# Inverter.net
KiCad netlist of a schematic drawn in Altium Designer
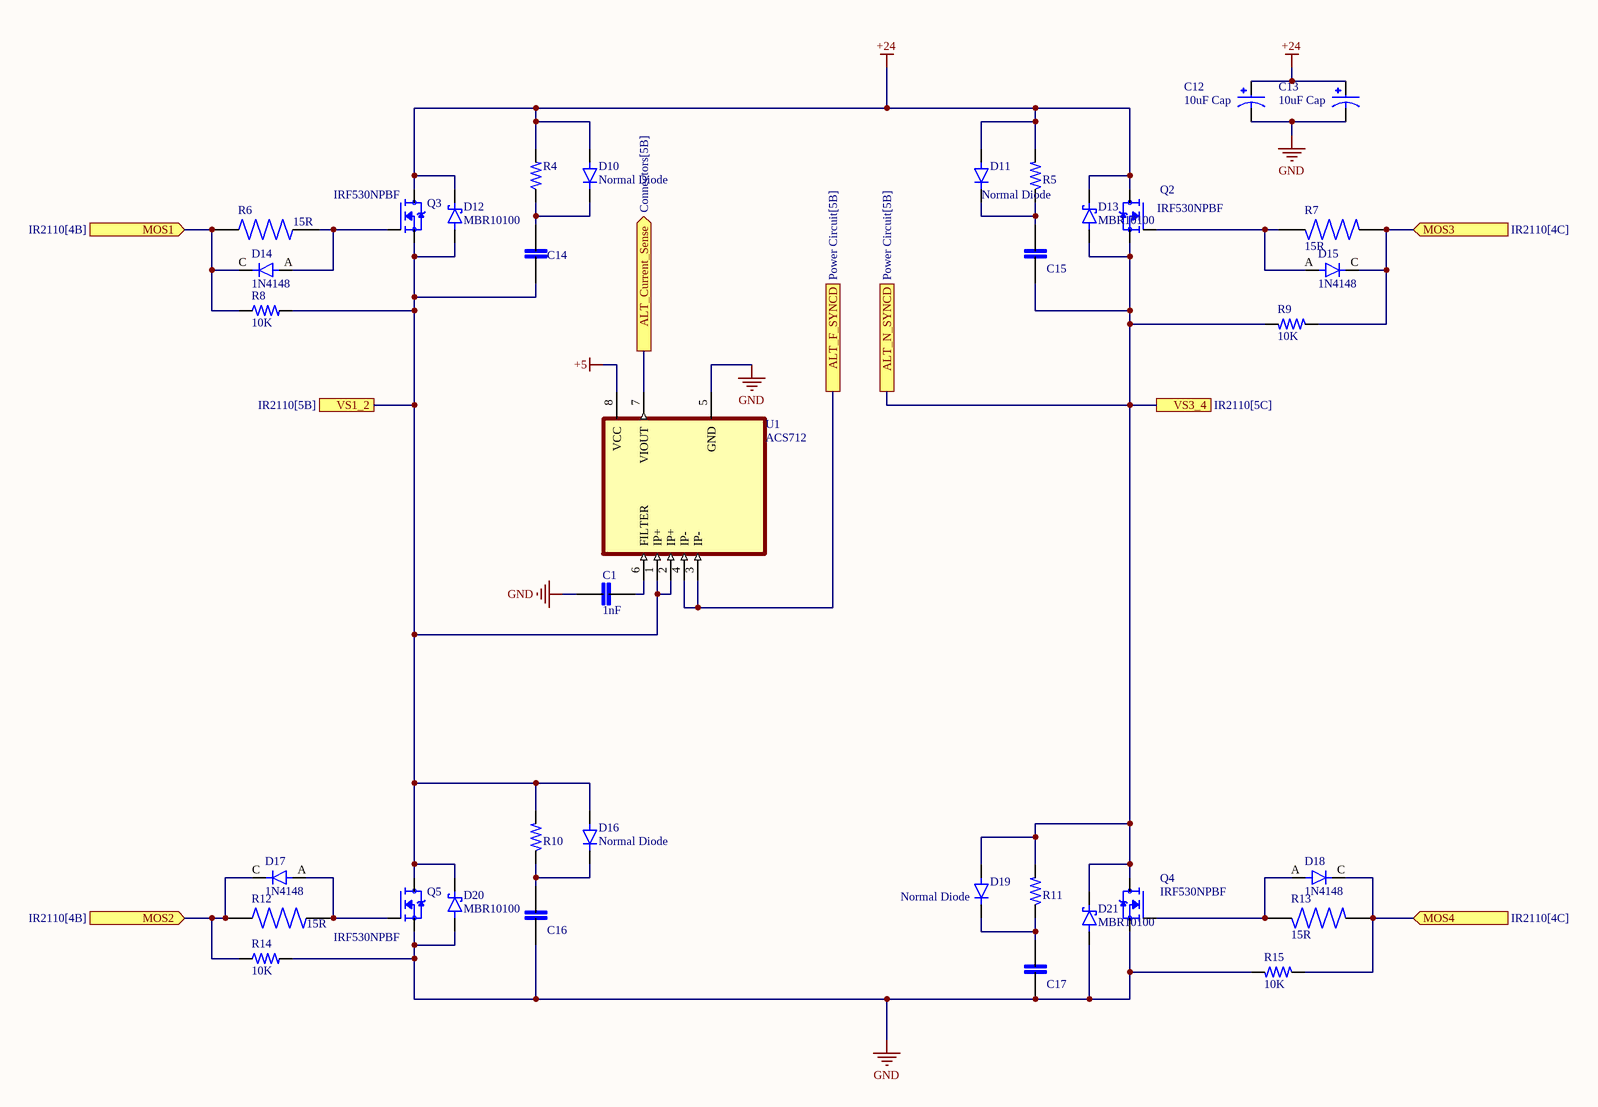
[diagram p0: Inverter.SchDoc]

(export (version "E")
  (design (tool "Eeschema 10.0.6"))
  (components
    (comp (ref "C1")
      (value "1nF")
      (footprint "Ceramic Capacitor")
      (fields (field (name "MP") "LD051A121KAB2A") (field (name "MF") "AVX"))
      (libsource (lib "Capacitors Through Hole") (part "Ceramic Capacitor"))
    )
    (comp (ref "C12")
      (value "10uF Cap")
      (footprint "2200uF_Cap")
      (description "CAP ALUM 10UF 20% 50V RADIAL")
      (fields (field (name "MP") "ECE-A1HN100UI") (field (name "MF") "Panasonic"))
      (libsource (lib "MySCH_Library") (part "10uF Cap"))
    )
    (comp (ref "C13")
      (value "10uF Cap")
      (footprint "2200uF_Cap")
      (description "CAP ALUM 10UF 20% 50V RADIAL")
      (fields (field (name "MP") "ECE-A1HN100UI") (field (name "MF") "Panasonic"))
      (libsource (lib "MySCH_Library") (part "10uF Cap"))
    )
    (comp (ref "C14")
      (value "Ceramic Capacitor")
      (footprint "Ceramic Capacitor")
      (fields (field (name "MP") "LD051A121KAB2A") (field (name "MF") "AVX"))
      (libsource (lib "") (part "Ceramic Capacitor_1"))
    )
    (comp (ref "C15")
      (value "Ceramic Capacitor")
      (footprint "Ceramic Capacitor")
      (fields (field (name "MP") "LD051A121KAB2A") (field (name "MF") "AVX"))
      (libsource (lib "Capacitors Through Hole") (part "Ceramic Capacitor"))
    )
    (comp (ref "C16")
      (value "Ceramic Capacitor")
      (footprint "Ceramic Capacitor")
      (fields (field (name "MP") "LD051A121KAB2A") (field (name "MF") "AVX"))
      (libsource (lib "Capacitors Through Hole") (part "Ceramic Capacitor"))
    )
    (comp (ref "C17")
      (value "Ceramic Capacitor")
      (footprint "Ceramic Capacitor")
      (fields (field (name "MP") "LD051A121KAB2A") (field (name "MF") "AVX"))
      (libsource (lib "Capacitors Through Hole") (part "Ceramic Capacitor"))
    )
    (comp (ref "D10")
      (value "Normal Diode")
      (footprint "Common Trhough Hole")
      (fields (field (name "MF") "NTE Electronics, Inc.") (field (name "MP") "1N4007"))
      (libsource (lib "Diodes Through Hole") (part "Normal Diode"))
    )
    (comp (ref "D11")
      (value "Normal Diode")
      (footprint "Common Trhough Hole")
      (fields (field (name "MF") "NTE Electronics, Inc.") (field (name "MP") "1N4007"))
      (libsource (lib "Diodes Through Hole") (part "Normal Diode"))
    )
    (comp (ref "D12")
      (value "MBR10100")
      (footprint "MBR10100")
      (fields (field (name "MF") "Diodes Inc.") (field (name "MP") "1N5817-T"))
      (libsource (lib "Diodes Through Hole") (part "MBR10100"))
    )
    (comp (ref "D13")
      (value "MBR10100")
      (footprint "MBR10100")
      (fields (field (name "MF") "Diodes Inc.") (field (name "MP") "1N5817-T"))
      (libsource (lib "Diodes Through Hole") (part "MBR10100"))
    )
    (comp (ref "D14")
      (value "1N4148")
      (footprint "1N4007 DIODE")
      (description "Diode Standard 1000 V 1A Through Hole DO-41")
      (fields (field (name "MF") "NTE Electronics, Inc.") (field (name "MP") "1N4007"))
      (libsource (lib "MySCH_Library") (part "1N4007"))
    )
    (comp (ref "D15")
      (value "1N4148")
      (footprint "1N4007 DIODE")
      (description "Diode Standard 1000 V 1A Through Hole DO-41")
      (fields (field (name "MF") "NTE Electronics, Inc.") (field (name "MP") "1N4007"))
      (libsource (lib "MySCH_Library") (part "1N4007"))
    )
    (comp (ref "D16")
      (value "Normal Diode")
      (footprint "Common Trhough Hole")
      (fields (field (name "MF") "NTE Electronics, Inc.") (field (name "MP") "1N4007"))
      (libsource (lib "Diodes Through Hole") (part "Normal Diode"))
    )
    (comp (ref "D17")
      (value "1N4148")
      (footprint "1N4007 DIODE")
      (description "Diode Standard 1000 V 1A Through Hole DO-41")
      (fields (field (name "MF") "NTE Electronics, Inc.") (field (name "MP") "1N4007"))
      (libsource (lib "MySCH_Library") (part "1N4007"))
    )
    (comp (ref "D18")
      (value "1N4148")
      (footprint "1N4007 DIODE")
      (description "Diode Standard 1000 V 1A Through Hole DO-41")
      (fields (field (name "MF") "NTE Electronics, Inc.") (field (name "MP") "1N4007"))
      (libsource (lib "MySCH_Library") (part "1N4007"))
    )
    (comp (ref "D19")
      (value "Normal Diode")
      (footprint "Common Trhough Hole")
      (fields (field (name "MF") "NTE Electronics, Inc.") (field (name "MP") "1N4007"))
      (libsource (lib "Diodes Through Hole") (part "Normal Diode"))
    )
    (comp (ref "D20")
      (value "MBR10100")
      (footprint "MBR10100")
      (fields (field (name "MF") "Diodes Inc.") (field (name "MP") "1N5817-T"))
      (libsource (lib "Diodes Through Hole") (part "MBR10100"))
    )
    (comp (ref "D21")
      (value "MBR10100")
      (footprint "MBR10100")
      (fields (field (name "MF") "Diodes Inc.") (field (name "MP") "1N5817-T"))
      (libsource (lib "Diodes Through Hole") (part "MBR10100"))
    )
    (comp (ref "Q2")
      (value "IRF530NPBF")
      (footprint "IRF530N")
      (fields (field (name "MF") "Infineon Technologies"))
      (libsource (lib "MySCH_Library") (part "IRF530NPBF"))
    )
    (comp (ref "Q3")
      (value "IRF530NPBF")
      (footprint "IRF530N")
      (fields (field (name "MF") "Infineon Technologies"))
      (libsource (lib "MySCH_Library") (part "IRF530NPBF"))
    )
    (comp (ref "Q4")
      (value "IRF530NPBF")
      (footprint "IRF530N")
      (fields (field (name "MF") "Infineon Technologies"))
      (libsource (lib "MySCH_Library") (part "IRF530NPBF"))
    )
    (comp (ref "Q5")
      (value "IRF530NPBF")
      (footprint "IRF530N")
      (fields (field (name "MF") "Infineon Technologies"))
      (libsource (lib "MySCH_Library") (part "IRF530NPBF"))
    )
    (comp (ref "R4")
      (value "Resistor")
      (footprint "Resistor_Through Hole")
      (fields
        (field (name "MP") "2-2176053-0")
        (field (name "TOLERANCE") "1%")
        (field (name "MF") "TE Connectivity")
      )
      (libsource (lib "Resistors Through Hole") (part "Resistor"))
    )
    (comp (ref "R5")
      (value "Resistor")
      (footprint "Resistor_Through Hole")
      (fields
        (field (name "MP") "2-2176053-0")
        (field (name "TOLERANCE") "1%")
        (field (name "MF") "TE Connectivity")
      )
      (libsource (lib "Resistors Through Hole") (part "Resistor"))
    )
    (comp (ref "R6")
      (value "15R")
      (footprint "Resistor_Through Hole")
      (description "1.02 Ohms Â±1% 0.25W, 1/4W Through Hole Resistor Axial Metal Film")
      (fields (field (name "MP") "MFR-25FTE52-1R") (field (name "MF") "Yageo"))
      (libsource (lib "MySCH_Library") (part "Resistor_Through Hole"))
    )
    (comp (ref "R7")
      (value "15R")
      (footprint "Resistor_Through Hole")
      (description "1.02 Ohms Â±1% 0.25W, 1/4W Through Hole Resistor Axial Metal Film")
      (fields (field (name "MP") "MFR-25FTE52-1R") (field (name "MF") "Yageo"))
      (libsource (lib "MySCH_Library") (part "Resistor_Through Hole"))
    )
    (comp (ref "R8")
      (value "10K")
      (footprint "Resistor_Through Hole")
      (fields
        (field (name "MP") "2-2176053-0")
        (field (name "TOLERANCE") "1%")
        (field (name "MF") "TE Connectivity")
      )
      (libsource (lib "Resistors Through Hole") (part "Resistor"))
    )
    (comp (ref "R9")
      (value "10K")
      (footprint "Resistor_Through Hole")
      (fields
        (field (name "MP") "2-2176053-0")
        (field (name "TOLERANCE") "1%")
        (field (name "MF") "TE Connectivity")
      )
      (libsource (lib "Resistors Through Hole") (part "Resistor"))
    )
    (comp (ref "R10")
      (value "Resistor")
      (footprint "Resistor_Through Hole")
      (fields
        (field (name "MP") "2-2176053-0")
        (field (name "TOLERANCE") "1%")
        (field (name "MF") "TE Connectivity")
      )
      (libsource (lib "Resistors Through Hole") (part "Resistor"))
    )
    (comp (ref "R11")
      (value "Resistor")
      (footprint "Resistor_Through Hole")
      (fields
        (field (name "MP") "2-2176053-0")
        (field (name "TOLERANCE") "1%")
        (field (name "MF") "TE Connectivity")
      )
      (libsource (lib "Resistors Through Hole") (part "Resistor"))
    )
    (comp (ref "R12")
      (value "15R")
      (footprint "Resistor_Through Hole")
      (description "1.02 Ohms Â±1% 0.25W, 1/4W Through Hole Resistor Axial Metal Film")
      (fields (field (name "MP") "MFR-25FTE52-1R") (field (name "MF") "Yageo"))
      (libsource (lib "MySCH_Library") (part "Resistor_Through Hole"))
    )
    (comp (ref "R13")
      (value "15R")
      (footprint "Resistor_Through Hole")
      (description "1.02 Ohms Â±1% 0.25W, 1/4W Through Hole Resistor Axial Metal Film")
      (fields (field (name "MP") "MFR-25FTE52-1R") (field (name "MF") "Yageo"))
      (libsource (lib "MySCH_Library") (part "Resistor_Through Hole"))
    )
    (comp (ref "R14")
      (value "10K")
      (footprint "Resistor_Through Hole")
      (fields
        (field (name "MP") "2-2176053-0")
        (field (name "TOLERANCE") "1%")
        (field (name "MF") "TE Connectivity")
      )
      (libsource (lib "Resistors Through Hole") (part "Resistor"))
    )
    (comp (ref "R15")
      (value "10K")
      (footprint "Resistor_Through Hole")
      (fields
        (field (name "MP") "2-2176053-0")
        (field (name "TOLERANCE") "1%")
        (field (name "MF") "TE Connectivity")
      )
      (libsource (lib "Resistors Through Hole") (part "Resistor"))
    )
    (comp (ref "U1")
      (value "ACS712")
      (footprint "ACS712")
      (description "Current Sensor 5A 1 Channel Hall Effect, Open Loop Bidirectional 8-SOIC (0.154, 3.90mm Width)")
      (fields (field (name "MP") "ACS712ELCTR-05B-T") (field (name "MF") "Allegro MicroSystems LLC"))
      (libsource (lib "Hall Current Sensor") (part "ACS712"))
    )
  )
  (nets
    (net (code "1") (name "+5") (class "Default")
      (node (ref "U1") (pin "8") (pinfunction "VCC_8") (pintype "power_in"))
    )
    (net (code "2") (name "+24") (class "Default")
      (node (ref "C12") (pin "P") (pinfunction "P_P") (pintype "passive"))
      (node (ref "C13") (pin "P") (pinfunction "P_P") (pintype "passive"))
      (node (ref "D10") (pin "2") (pinfunction "A_2") (pintype "passive"))
      (node (ref "D11") (pin "2") (pinfunction "A_2") (pintype "passive"))
      (node (ref "D12") (pin "1") (pinfunction "K_1") (pintype "passive"))
      (node (ref "D13") (pin "1") (pinfunction "K_1") (pintype "passive"))
      (node (ref "Q2") (pin "2") (pinfunction "D_2") (pintype "passive"))
      (node (ref "Q3") (pin "2") (pinfunction "D_2") (pintype "passive"))
      (node (ref "R4") (pin "2") (pinfunction "2_2") (pintype "passive"))
      (node (ref "R5") (pin "2") (pinfunction "2_2") (pintype "passive"))
    )
    (net (code "3") (name "/ALT_Current_Sense") (class "Default")
      (node (ref "U1") (pin "7") (pinfunction "VIOUT_7") (pintype "output"))
    )
    (net (code "4") (name "/ALT_F_SYNCD") (class "Default")
      (node (ref "U1") (pin "3") (pinfunction "IP-_3") (pintype "input"))
      (node (ref "U1") (pin "4") (pinfunction "IP-_4") (pintype "input"))
    )
    (net (code "5") (name "/ALT_N_SYNCD") (class "Default")
      (node (ref "C15") (pin "1") (pinfunction "1_1") (pintype "passive"))
      (node (ref "D13") (pin "3") (pinfunction "A_3") (pintype "passive"))
      (node (ref "D19") (pin "2") (pinfunction "A_2") (pintype "passive"))
      (node (ref "D21") (pin "1") (pinfunction "K_1") (pintype "passive"))
      (node (ref "Q2") (pin "3") (pinfunction "S_3") (pintype "passive"))
      (node (ref "Q4") (pin "2") (pinfunction "D_2") (pintype "passive"))
      (node (ref "R11") (pin "2") (pinfunction "2_2") (pintype "passive"))
      (node (ref "R9") (pin "2") (pinfunction "2_2") (pintype "passive"))
    )
    (net (code "6") (name "/MOS1") (class "Default")
      (node (ref "D14") (pin "C") (pinfunction "C_C") (pintype "passive"))
      (node (ref "R6") (pin "1") (pinfunction "1_1") (pintype "passive"))
      (node (ref "R8") (pin "1") (pinfunction "1_1") (pintype "passive"))
    )
    (net (code "7") (name "/MOS2") (class "Default")
      (node (ref "D17") (pin "C") (pinfunction "C_C") (pintype "passive"))
      (node (ref "R12") (pin "1") (pinfunction "1_1") (pintype "passive"))
      (node (ref "R14") (pin "1") (pinfunction "1_1") (pintype "passive"))
    )
    (net (code "8") (name "/MOS3") (class "Default")
      (node (ref "D15") (pin "C") (pinfunction "C_C") (pintype "passive"))
      (node (ref "R7") (pin "1") (pinfunction "1_1") (pintype "passive"))
      (node (ref "R9") (pin "1") (pinfunction "1_1") (pintype "passive"))
    )
    (net (code "9") (name "/MOS4") (class "Default")
      (node (ref "D18") (pin "C") (pinfunction "C_C") (pintype "passive"))
      (node (ref "R13") (pin "1") (pinfunction "1_1") (pintype "passive"))
      (node (ref "R15") (pin "1") (pinfunction "1_1") (pintype "passive"))
    )
    (net (code "10") (name "/VS1_2") (class "Default")
      (node (ref "C14") (pin "1") (pinfunction "1_1") (pintype "passive"))
      (node (ref "D12") (pin "3") (pinfunction "A_3") (pintype "passive"))
      (node (ref "D16") (pin "2") (pinfunction "A_2") (pintype "passive"))
      (node (ref "D20") (pin "1") (pinfunction "K_1") (pintype "passive"))
      (node (ref "Q3") (pin "3") (pinfunction "S_3") (pintype "passive"))
      (node (ref "Q5") (pin "2") (pinfunction "D_2") (pintype "passive"))
      (node (ref "R10") (pin "2") (pinfunction "2_2") (pintype "passive"))
      (node (ref "R8") (pin "2") (pinfunction "2_2") (pintype "passive"))
      (node (ref "U1") (pin "1") (pinfunction "IP+_1") (pintype "input"))
      (node (ref "U1") (pin "2") (pinfunction "IP+_2") (pintype "input"))
    )
    (net (code "11") (name "GND") (class "Default")
      (node (ref "C1") (pin "1") (pinfunction "1_1") (pintype "passive"))
      (node (ref "C12") (pin "N") (pinfunction "N_N") (pintype "passive"))
      (node (ref "C13") (pin "N") (pinfunction "N_N") (pintype "passive"))
      (node (ref "C16") (pin "1") (pinfunction "1_1") (pintype "passive"))
      (node (ref "C17") (pin "1") (pinfunction "1_1") (pintype "passive"))
      (node (ref "D20") (pin "3") (pinfunction "A_3") (pintype "passive"))
      (node (ref "D21") (pin "3") (pinfunction "A_3") (pintype "passive"))
      (node (ref "Q4") (pin "3") (pinfunction "S_3") (pintype "passive"))
      (node (ref "Q5") (pin "3") (pinfunction "S_3") (pintype "passive"))
      (node (ref "R14") (pin "2") (pinfunction "2_2") (pintype "passive"))
      (node (ref "R15") (pin "2") (pinfunction "2_2") (pintype "passive"))
      (node (ref "U1") (pin "5") (pinfunction "GND_5") (pintype "power_in"))
    )
    (net (code "12") (name "Net-(D10-K)") (class "Default")
      (node (ref "C14") (pin "2") (pinfunction "2_2") (pintype "passive"))
      (node (ref "D10") (pin "1") (pinfunction "K_1") (pintype "passive"))
      (node (ref "R4") (pin "1") (pinfunction "1_1") (pintype "passive"))
    )
    (net (code "13") (name "Net-(D11-K)") (class "Default")
      (node (ref "C15") (pin "2") (pinfunction "2_2") (pintype "passive"))
      (node (ref "D11") (pin "1") (pinfunction "K_1") (pintype "passive"))
      (node (ref "R5") (pin "1") (pinfunction "1_1") (pintype "passive"))
    )
    (net (code "14") (name "Net-(D16-K)") (class "Default")
      (node (ref "C16") (pin "2") (pinfunction "2_2") (pintype "passive"))
      (node (ref "D16") (pin "1") (pinfunction "K_1") (pintype "passive"))
      (node (ref "R10") (pin "1") (pinfunction "1_1") (pintype "passive"))
    )
    (net (code "15") (name "Net-(D19-K)") (class "Default")
      (node (ref "C17") (pin "2") (pinfunction "2_2") (pintype "passive"))
      (node (ref "D19") (pin "1") (pinfunction "K_1") (pintype "passive"))
      (node (ref "R11") (pin "1") (pinfunction "1_1") (pintype "passive"))
    )
    (net (code "16") (name "Net-(Q2-G)") (class "Default")
      (node (ref "D15") (pin "A") (pinfunction "A_A") (pintype "passive"))
      (node (ref "Q2") (pin "1") (pinfunction "G_1") (pintype "passive"))
      (node (ref "R7") (pin "2") (pinfunction "2_2") (pintype "passive"))
    )
    (net (code "17") (name "Net-(Q3-G)") (class "Default")
      (node (ref "D14") (pin "A") (pinfunction "A_A") (pintype "passive"))
      (node (ref "Q3") (pin "1") (pinfunction "G_1") (pintype "passive"))
      (node (ref "R6") (pin "2") (pinfunction "2_2") (pintype "passive"))
    )
    (net (code "18") (name "Net-(Q4-G)") (class "Default")
      (node (ref "D18") (pin "A") (pinfunction "A_A") (pintype "passive"))
      (node (ref "Q4") (pin "1") (pinfunction "G_1") (pintype "passive"))
      (node (ref "R13") (pin "2") (pinfunction "2_2") (pintype "passive"))
    )
    (net (code "19") (name "Net-(Q5-G)") (class "Default")
      (node (ref "D17") (pin "A") (pinfunction "A_A") (pintype "passive"))
      (node (ref "Q5") (pin "1") (pinfunction "G_1") (pintype "passive"))
      (node (ref "R12") (pin "2") (pinfunction "2_2") (pintype "passive"))
    )
    (net (code "20") (name "Net-(U1-FILTER)") (class "Default")
      (node (ref "C1") (pin "2") (pinfunction "2_2") (pintype "passive"))
      (node (ref "U1") (pin "6") (pinfunction "FILTER_6") (pintype "input"))
    )
  )
)
